# GaN_PLL.net
KiCad netlist of a schematic drawn in Altium Designer
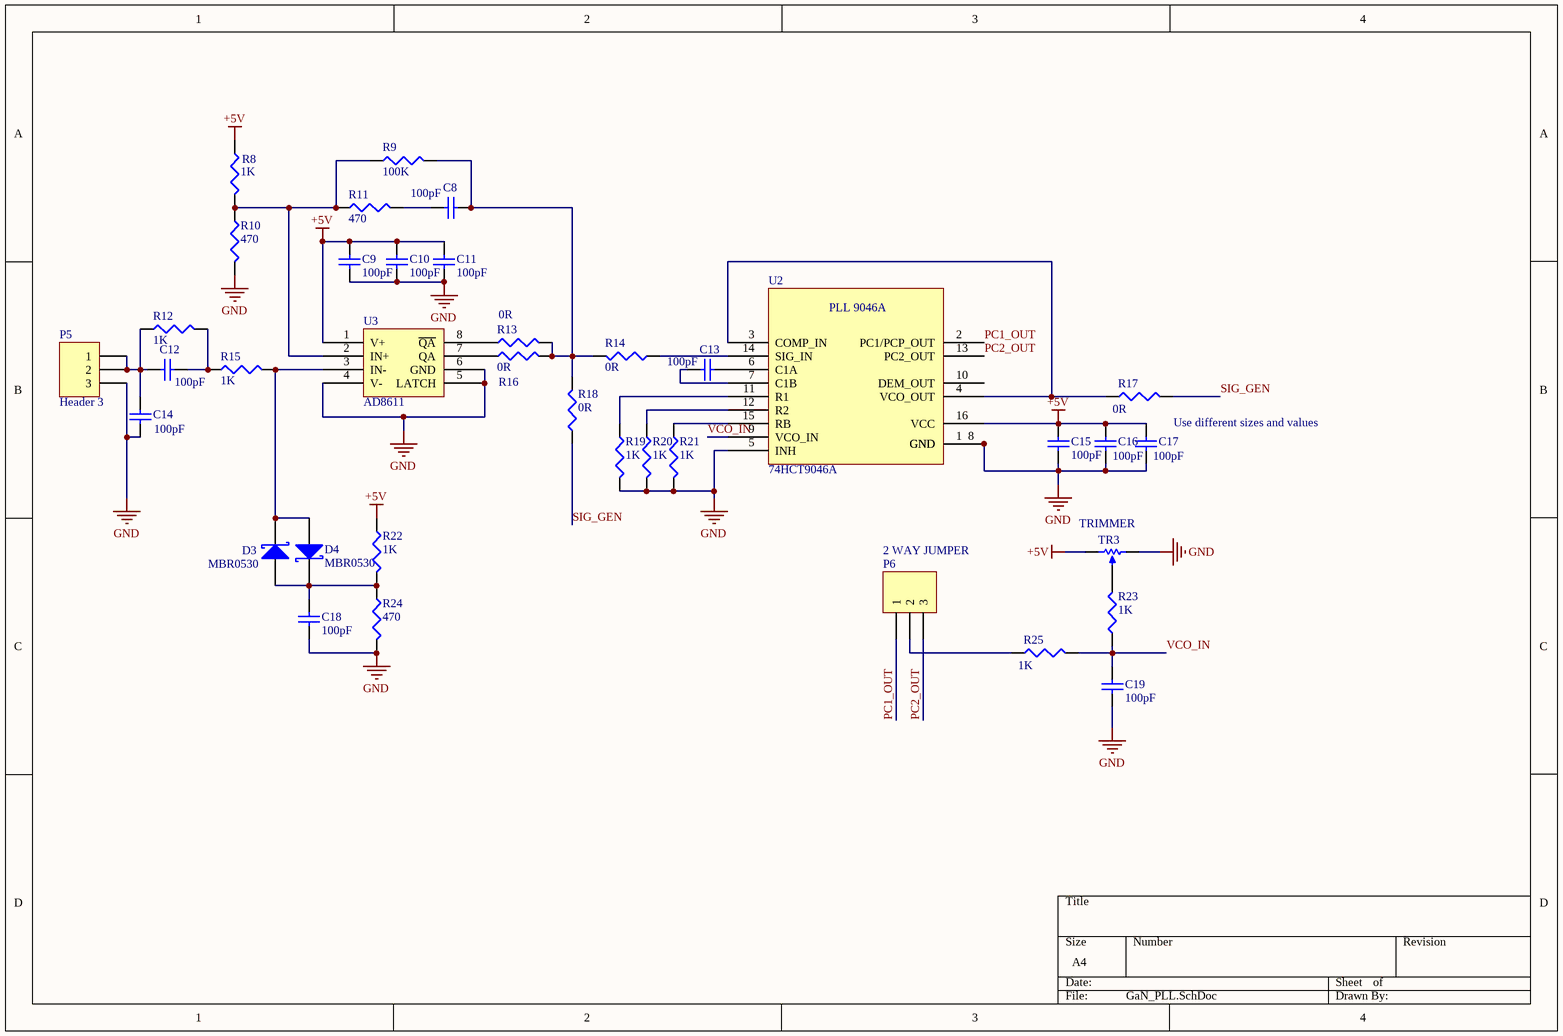
[diagram p0: GaN_PLL.SchDoc]

(export (version "E")
  (design (tool "Eeschema 10.0.6"))
  (components
    (comp (ref "C8")
      (value "100pF")
      (footprint "0603 IPC Low Density")
      (description "Capacitor (Semiconductor SIM Model)")
      (fields (field (name "Comment") "Cap Semi") (field (name "PUBLISHER") "Altium Limited"))
      (libsource (lib "Miscellaneous Devices") (part "Cap Semi"))
    )
    (comp (ref "C9")
      (value "100pF")
      (footprint "0603 IPC Low Density")
      (description "Capacitor (Semiconductor SIM Model)")
      (fields (field (name "Comment") "Cap Semi") (field (name "PUBLISHER") "Altium Limited"))
      (libsource (lib "Miscellaneous Devices") (part "Cap Semi"))
    )
    (comp (ref "C10")
      (value "100pF")
      (footprint "0603 IPC Low Density")
      (description "Capacitor (Semiconductor SIM Model)")
      (fields (field (name "Comment") "Cap Semi") (field (name "PUBLISHER") "Altium Limited"))
      (libsource (lib "Miscellaneous Devices") (part "Cap Semi"))
    )
    (comp (ref "C11")
      (value "100pF")
      (footprint "0603 IPC Low Density")
      (description "Capacitor (Semiconductor SIM Model)")
      (fields (field (name "Comment") "Cap Semi") (field (name "PUBLISHER") "Altium Limited"))
      (libsource (lib "Miscellaneous Devices") (part "Cap Semi"))
    )
    (comp (ref "C12")
      (value "100pF")
      (footprint "0603 IPC Low Density")
      (description "Capacitor (Semiconductor SIM Model)")
      (fields (field (name "Comment") "Cap Semi") (field (name "PUBLISHER") "Altium Limited"))
      (libsource (lib "Miscellaneous Devices") (part "Cap Semi"))
    )
    (comp (ref "C13")
      (value "100pF")
      (footprint "0603 IPC Low Density")
      (description "Capacitor (Semiconductor SIM Model)")
      (fields (field (name "Comment") "Cap Semi") (field (name "PUBLISHER") "Altium Limited"))
      (libsource (lib "Miscellaneous Devices") (part "Cap Semi"))
    )
    (comp (ref "C14")
      (value "100pF")
      (footprint "0805 IPC Low Density")
      (description "Capacitor (Semiconductor SIM Model)")
      (fields (field (name "Comment") "Cap Semi") (field (name "PUBLISHER") "Altium Limited"))
      (libsource (lib "Miscellaneous Devices") (part "Cap Semi"))
    )
    (comp (ref "C15")
      (value "100pF")
      (footprint "0603 IPC Low Density")
      (description "Capacitor (Semiconductor SIM Model)")
      (fields (field (name "Comment") "Cap Semi") (field (name "PUBLISHER") "Altium Limited"))
      (libsource (lib "Miscellaneous Devices") (part "Cap Semi"))
    )
    (comp (ref "C16")
      (value "100pF")
      (footprint "0603 IPC Low Density")
      (description "Capacitor (Semiconductor SIM Model)")
      (fields (field (name "Comment") "Cap Semi") (field (name "PUBLISHER") "Altium Limited"))
      (libsource (lib "Miscellaneous Devices") (part "Cap Semi"))
    )
    (comp (ref "C17")
      (value "100pF")
      (footprint "0603 IPC Low Density")
      (description "Capacitor (Semiconductor SIM Model)")
      (fields (field (name "Comment") "Cap Semi") (field (name "PUBLISHER") "Altium Limited"))
      (libsource (lib "Miscellaneous Devices") (part "Cap Semi"))
    )
    (comp (ref "C18")
      (value "100pF")
      (footprint "0805 IPC Low Density")
      (description "Capacitor (Semiconductor SIM Model)")
      (fields (field (name "Comment") "Cap Semi") (field (name "PUBLISHER") "Altium Limited"))
      (libsource (lib "Miscellaneous Devices") (part "Cap Semi"))
    )
    (comp (ref "C19")
      (value "100pF")
      (footprint "0603 IPC Low Density")
      (description "Capacitor (Semiconductor SIM Model)")
      (fields (field (name "Comment") "Cap Semi") (field (name "PUBLISHER") "Altium Limited"))
      (libsource (lib "Miscellaneous Devices") (part "Cap Semi"))
    )
    (comp (ref "D3")
      (value "MBR0530")
      (footprint "SOD-123")
      (description "Schottky Rectifier, SOD-123")
      (libsource (lib "GaN_Schlib") (part "MBR0530"))
    )
    (comp (ref "D4")
      (value "MBR0530")
      (footprint "SOD-123")
      (description "Schottky Rectifier, SOD-123")
      (libsource (lib "GaN_Schlib") (part "MBR0530"))
    )
    (comp (ref "P5")
      (value "Header 3")
      (footprint "HDR1X3")
      (description "Header, 3-Pin")
      (fields (field (name "PUBLISHER") "Altium Limited"))
      (libsource (lib "Miscellaneous Connectors") (part "Header 3"))
    )
    (comp (ref "P6")
      (value "2 WAY JUMPER")
      (footprint "2 WAY JUMPER")
      (fields (field (name "PUBLISHER") "Altium Limited"))
      (libsource (lib "GaN_Schlib") (part "Header 3"))
    )
    (comp (ref "R8")
      (value "1K")
      (footprint "RESISTOR 0603")
      (description "Resistor")
      (fields (field (name "Comment") "Res3") (field (name "PUBLISHER") "Altium Limited"))
      (libsource (lib "Miscellaneous Devices") (part "Res3"))
    )
    (comp (ref "R9")
      (value "100K")
      (footprint "RESISTOR 0603")
      (description "Resistor")
      (fields (field (name "Comment") "Res3") (field (name "PUBLISHER") "Altium Limited"))
      (libsource (lib "Miscellaneous Devices") (part "Res3"))
    )
    (comp (ref "R10")
      (value "470")
      (footprint "RESISTOR 0603")
      (description "Resistor")
      (fields (field (name "Comment") "Res3") (field (name "PUBLISHER") "Altium Limited"))
      (libsource (lib "Miscellaneous Devices") (part "Res3"))
    )
    (comp (ref "R11")
      (value "470")
      (footprint "RESISTOR 0603")
      (description "Resistor")
      (fields (field (name "Comment") "Res3") (field (name "PUBLISHER") "Altium Limited"))
      (libsource (lib "Miscellaneous Devices") (part "Res3"))
    )
    (comp (ref "R12")
      (value "1K")
      (footprint "RESISTOR 0603")
      (description "Resistor")
      (fields (field (name "Comment") "Res3") (field (name "PUBLISHER") "Altium Limited"))
      (libsource (lib "Miscellaneous Devices") (part "Res3"))
    )
    (comp (ref "R13")
      (value "0R")
      (footprint "RESISTOR 0603")
      (description "Resistor")
      (fields (field (name "Comment") "Res3") (field (name "PUBLISHER") "Altium Limited"))
      (libsource (lib "Miscellaneous Devices") (part "Res3"))
    )
    (comp (ref "R14")
      (value "0R")
      (footprint "RESISTOR 0603")
      (description "Resistor")
      (fields (field (name "Comment") "Res3") (field (name "PUBLISHER") "Altium Limited"))
      (libsource (lib "Miscellaneous Devices") (part "Res3"))
    )
    (comp (ref "R15")
      (value "1K")
      (footprint "RESISTOR 0603")
      (description "Resistor")
      (fields (field (name "Comment") "Res3") (field (name "PUBLISHER") "Altium Limited"))
      (libsource (lib "Miscellaneous Devices") (part "Res3"))
    )
    (comp (ref "R16")
      (value "0R")
      (footprint "RESISTOR 0603")
      (description "Resistor")
      (fields (field (name "Comment") "Res3") (field (name "PUBLISHER") "Altium Limited"))
      (libsource (lib "Miscellaneous Devices") (part "Res3"))
    )
    (comp (ref "R17")
      (value "0R")
      (footprint "RESISTOR 0603")
      (description "Resistor")
      (fields (field (name "Comment") "Res3") (field (name "PUBLISHER") "Altium Limited"))
      (libsource (lib "Miscellaneous Devices") (part "Res3"))
    )
    (comp (ref "R18")
      (value "0R")
      (footprint "RESISTOR 0603")
      (description "Resistor")
      (fields (field (name "Comment") "Res3") (field (name "PUBLISHER") "Altium Limited"))
      (libsource (lib "Miscellaneous Devices") (part "Res3"))
    )
    (comp (ref "R19")
      (value "1K")
      (footprint "RESISTOR 0603")
      (description "Resistor")
      (fields (field (name "Comment") "Res3") (field (name "PUBLISHER") "Altium Limited"))
      (libsource (lib "Miscellaneous Devices") (part "Res3"))
    )
    (comp (ref "R20")
      (value "1K")
      (footprint "RESISTOR 0603")
      (description "Resistor")
      (fields (field (name "Comment") "Res3") (field (name "PUBLISHER") "Altium Limited"))
      (libsource (lib "Miscellaneous Devices") (part "Res3"))
    )
    (comp (ref "R21")
      (value "1K")
      (footprint "RESISTOR 0603")
      (description "Resistor")
      (fields (field (name "Comment") "Res3") (field (name "PUBLISHER") "Altium Limited"))
      (libsource (lib "Miscellaneous Devices") (part "Res3"))
    )
    (comp (ref "R22")
      (value "1K")
      (footprint "RESISTOR 0603")
      (description "Resistor")
      (fields (field (name "Comment") "Res3") (field (name "PUBLISHER") "Altium Limited"))
      (libsource (lib "Miscellaneous Devices") (part "Res3"))
    )
    (comp (ref "R23")
      (value "1K")
      (footprint "RESISTOR 0603")
      (description "Resistor")
      (fields (field (name "Comment") "Res3") (field (name "PUBLISHER") "Altium Limited"))
      (libsource (lib "Miscellaneous Devices") (part "Res3"))
    )
    (comp (ref "R24")
      (value "470")
      (footprint "RESISTOR 0603")
      (description "Resistor")
      (fields (field (name "Comment") "Res3") (field (name "PUBLISHER") "Altium Limited"))
      (libsource (lib "Miscellaneous Devices") (part "Res3"))
    )
    (comp (ref "R25")
      (value "1K")
      (footprint "RESISTOR 0603")
      (description "Resistor")
      (fields (field (name "Comment") "Res3") (field (name "PUBLISHER") "Altium Limited"))
      (libsource (lib "Miscellaneous Devices") (part "Res3"))
    )
    (comp (ref "TR3")
      (value "TRIMMER")
      (footprint "3296W")
      (libsource (lib "GaN_Schlib") (part "TRIMMER 3296W"))
    )
    (comp (ref "U2")
      (value "74HCT9046A")
      (footprint "SO16")
      (description "Phase Locked Loops - PLL PLL BAND GAP CNTRL W/VCO")
      (libsource (lib "GaN_Schlib") (part "74HCT9046A"))
    )
    (comp (ref "U3")
      (value "AD8611")
      (footprint "SOIC8_N")
      (description "Ultrafast, 4 ns Single-Supply Comparators")
      (libsource (lib "GaN_Schlib") (part "AD8611"))
    )
  )
  (nets
    (net (code "1") (name "+5V") (class "Default")
      (node (ref "C10") (pin "1") (pinfunction "1_1") (pintype "passive"))
      (node (ref "C11") (pin "1") (pinfunction "1_1") (pintype "passive"))
      (node (ref "C15") (pin "2") (pinfunction "2_2") (pintype "passive"))
      (node (ref "C16") (pin "2") (pinfunction "2_2") (pintype "passive"))
      (node (ref "C17") (pin "2") (pinfunction "2_2") (pintype "passive"))
      (node (ref "C9") (pin "1") (pinfunction "1_1") (pintype "passive"))
      (node (ref "R22") (pin "1") (pinfunction "1_1") (pintype "passive"))
      (node (ref "R8") (pin "1") (pinfunction "1_1") (pintype "passive"))
      (node (ref "TR3") (pin "1") (pinfunction "TOP_1") (pintype "passive"))
      (node (ref "U2") (pin "16") (pinfunction "VCC_16") (pintype "passive"))
      (node (ref "U3") (pin "1") (pinfunction "V+_1") (pintype "passive"))
    )
    (net (code "2") (name "/PC1_OUT") (class "Default")
      (node (ref "P6") (pin "1") (pinfunction "1_1") (pintype "passive"))
      (node (ref "U2") (pin "2") (pinfunction "PC1/PCP_OUT_2") (pintype "passive"))
    )
    (net (code "3") (name "/PC2_OUT") (class "Default")
      (node (ref "P6") (pin "3") (pinfunction "3_3") (pintype "passive"))
      (node (ref "U2") (pin "13") (pinfunction "PC2_OUT_13") (pintype "passive"))
    )
    (net (code "4") (name "/SIG_GEN") (class "Default")
      (node (ref "R17") (pin "2") (pinfunction "2_2") (pintype "passive"))
      (node (ref "R18") (pin "1") (pinfunction "1_1") (pintype "passive"))
    )
    (net (code "5") (name "/VCO_IN") (class "Default")
      (node (ref "C19") (pin "1") (pinfunction "1_1") (pintype "passive"))
      (node (ref "R23") (pin "1") (pinfunction "1_1") (pintype "passive"))
      (node (ref "R25") (pin "2") (pinfunction "2_2") (pintype "passive"))
      (node (ref "U2") (pin "9") (pinfunction "VCO_IN_9") (pintype "passive"))
    )
    (net (code "6") (name "GND") (class "Default")
      (node (ref "C10") (pin "2") (pinfunction "2_2") (pintype "passive"))
      (node (ref "C11") (pin "2") (pinfunction "2_2") (pintype "passive"))
      (node (ref "C14") (pin "1") (pinfunction "1_1") (pintype "passive"))
      (node (ref "C15") (pin "1") (pinfunction "1_1") (pintype "passive"))
      (node (ref "C16") (pin "1") (pinfunction "1_1") (pintype "passive"))
      (node (ref "C17") (pin "1") (pinfunction "1_1") (pintype "passive"))
      (node (ref "C18") (pin "1") (pinfunction "1_1") (pintype "passive"))
      (node (ref "C19") (pin "2") (pinfunction "2_2") (pintype "passive"))
      (node (ref "C9") (pin "2") (pinfunction "2_2") (pintype "passive"))
      (node (ref "P5") (pin "3") (pinfunction "3_3") (pintype "passive"))
      (node (ref "R10") (pin "2") (pinfunction "2_2") (pintype "passive"))
      (node (ref "R19") (pin "2") (pinfunction "2_2") (pintype "passive"))
      (node (ref "R20") (pin "2") (pinfunction "2_2") (pintype "passive"))
      (node (ref "R21") (pin "2") (pinfunction "2_2") (pintype "passive"))
      (node (ref "R24") (pin "2") (pinfunction "2_2") (pintype "passive"))
      (node (ref "TR3") (pin "3") (pinfunction "BOT_3") (pintype "passive"))
      (node (ref "U2") (pin "1") (pinfunction "GND_1") (pintype "passive"))
      (node (ref "U2") (pin "5") (pinfunction "INH_5") (pintype "passive"))
      (node (ref "U2") (pin "8") (pinfunction "GND_8") (pintype "passive"))
      (node (ref "U3") (pin "4") (pinfunction "V-_4") (pintype "passive"))
      (node (ref "U3") (pin "5") (pinfunction "LATCH_5") (pintype "passive"))
      (node (ref "U3") (pin "6") (pinfunction "GND_6") (pintype "passive"))
    )
    (net (code "7") (name "Net-(C8-Pad1)") (class "Default")
      (node (ref "C8") (pin "1") (pinfunction "1_1") (pintype "passive"))
      (node (ref "R13") (pin "2") (pinfunction "2_2") (pintype "passive"))
      (node (ref "R14") (pin "2") (pinfunction "2_2") (pintype "passive"))
      (node (ref "R16") (pin "2") (pinfunction "2_2") (pintype "passive"))
      (node (ref "R18") (pin "2") (pinfunction "2_2") (pintype "passive"))
      (node (ref "R9") (pin "2") (pinfunction "2_2") (pintype "passive"))
    )
    (net (code "8") (name "Net-(C8-Pad2)") (class "Default")
      (node (ref "C8") (pin "2") (pinfunction "2_2") (pintype "passive"))
      (node (ref "R11") (pin "2") (pinfunction "2_2") (pintype "passive"))
    )
    (net (code "9") (name "Net-(C12-Pad1)") (class "Default")
      (node (ref "C12") (pin "1") (pinfunction "1_1") (pintype "passive"))
      (node (ref "R12") (pin "2") (pinfunction "2_2") (pintype "passive"))
      (node (ref "R15") (pin "1") (pinfunction "1_1") (pintype "passive"))
    )
    (net (code "10") (name "Net-(C12-Pad2)") (class "Default")
      (node (ref "C12") (pin "2") (pinfunction "2_2") (pintype "passive"))
      (node (ref "C14") (pin "2") (pinfunction "2_2") (pintype "passive"))
      (node (ref "P5") (pin "1") (pinfunction "1_1") (pintype "passive"))
      (node (ref "P5") (pin "2") (pinfunction "2_2") (pintype "passive"))
      (node (ref "R12") (pin "1") (pinfunction "1_1") (pintype "passive"))
    )
    (net (code "11") (name "Net-(D3-A)") (class "Default")
      (node (ref "C18") (pin "2") (pinfunction "2_2") (pintype "passive"))
      (node (ref "D3") (pin "1") (pinfunction "A_1") (pintype "passive"))
      (node (ref "D4") (pin "3") (pinfunction "K_3") (pintype "passive"))
      (node (ref "R22") (pin "2") (pinfunction "2_2") (pintype "passive"))
      (node (ref "R24") (pin "1") (pinfunction "1_1") (pintype "passive"))
    )
    (net (code "12") (name "Net-(D3-K)") (class "Default")
      (node (ref "D3") (pin "3") (pinfunction "K_3") (pintype "passive"))
      (node (ref "D4") (pin "1") (pinfunction "A_1") (pintype "passive"))
      (node (ref "R15") (pin "2") (pinfunction "2_2") (pintype "passive"))
      (node (ref "U3") (pin "3") (pinfunction "IN-_3") (pintype "passive"))
    )
    (net (code "13") (name "Net-(P6-Pad2)") (class "Default")
      (node (ref "P6") (pin "2") (pinfunction "2_2") (pintype "passive"))
      (node (ref "R25") (pin "1") (pinfunction "1_1") (pintype "passive"))
    )
    (net (code "14") (name "Net-(R13-Pad1)") (class "Default")
      (node (ref "R13") (pin "1") (pinfunction "1_1") (pintype "passive"))
      (node (ref "U3") (pin "8") (pinfunction "QA_8") (pintype "passive"))
    )
    (net (code "15") (name "Net-(R16-Pad1)") (class "Default")
      (node (ref "R16") (pin "1") (pinfunction "1_1") (pintype "passive"))
      (node (ref "U3") (pin "7") (pinfunction "QA_7") (pintype "passive"))
    )
    (net (code "16") (name "Net-(TR3-TAP)") (class "Default")
      (node (ref "R23") (pin "2") (pinfunction "2_2") (pintype "passive"))
      (node (ref "TR3") (pin "2") (pinfunction "TAP_2") (pintype "passive"))
    )
    (net (code "17") (name "Net-(U2-C1A)") (class "Default")
      (node (ref "C13") (pin "1") (pinfunction "1_1") (pintype "passive"))
      (node (ref "U2") (pin "6") (pinfunction "C1A_6") (pintype "passive"))
    )
    (net (code "18") (name "Net-(U2-C1B)") (class "Default")
      (node (ref "C13") (pin "2") (pinfunction "2_2") (pintype "passive"))
      (node (ref "U2") (pin "7") (pinfunction "C1B_7") (pintype "passive"))
    )
    (net (code "19") (name "Net-(U2-COMP_IN)") (class "Default")
      (node (ref "R17") (pin "1") (pinfunction "1_1") (pintype "passive"))
      (node (ref "U2") (pin "3") (pinfunction "COMP_IN_3") (pintype "passive"))
      (node (ref "U2") (pin "4") (pinfunction "VCO_OUT_4") (pintype "passive"))
    )
    (net (code "20") (name "Net-(U2-R1)") (class "Default")
      (node (ref "R19") (pin "1") (pinfunction "1_1") (pintype "passive"))
      (node (ref "U2") (pin "11") (pinfunction "R1_11") (pintype "passive"))
    )
    (net (code "21") (name "Net-(U2-R2)") (class "Default")
      (node (ref "R20") (pin "1") (pinfunction "1_1") (pintype "passive"))
      (node (ref "U2") (pin "12") (pinfunction "R2_12") (pintype "passive"))
    )
    (net (code "22") (name "Net-(U2-RB)") (class "Default")
      (node (ref "R21") (pin "1") (pinfunction "1_1") (pintype "passive"))
      (node (ref "U2") (pin "15") (pinfunction "RB_15") (pintype "passive"))
    )
    (net (code "23") (name "Net-(U2-SIG_IN)") (class "Default")
      (node (ref "R14") (pin "1") (pinfunction "1_1") (pintype "passive"))
      (node (ref "U2") (pin "14") (pinfunction "SIG_IN_14") (pintype "passive"))
    )
    (net (code "24") (name "Net-(U3-IN+)") (class "Default")
      (node (ref "R10") (pin "1") (pinfunction "1_1") (pintype "passive"))
      (node (ref "R11") (pin "1") (pinfunction "1_1") (pintype "passive"))
      (node (ref "R8") (pin "2") (pinfunction "2_2") (pintype "passive"))
      (node (ref "R9") (pin "1") (pinfunction "1_1") (pintype "passive"))
      (node (ref "U3") (pin "2") (pinfunction "IN+_2") (pintype "passive"))
    )
    (net (code "25") (name "unconnected-(U2-DEM_OUT-Pad10)") (class "Default")
      (node (ref "U2") (pin "10") (pinfunction "DEM_OUT_10") (pintype "passive"))
    )
  )
)
